# relaysch.net
KiCad netlist of a schematic drawn in EAGLE
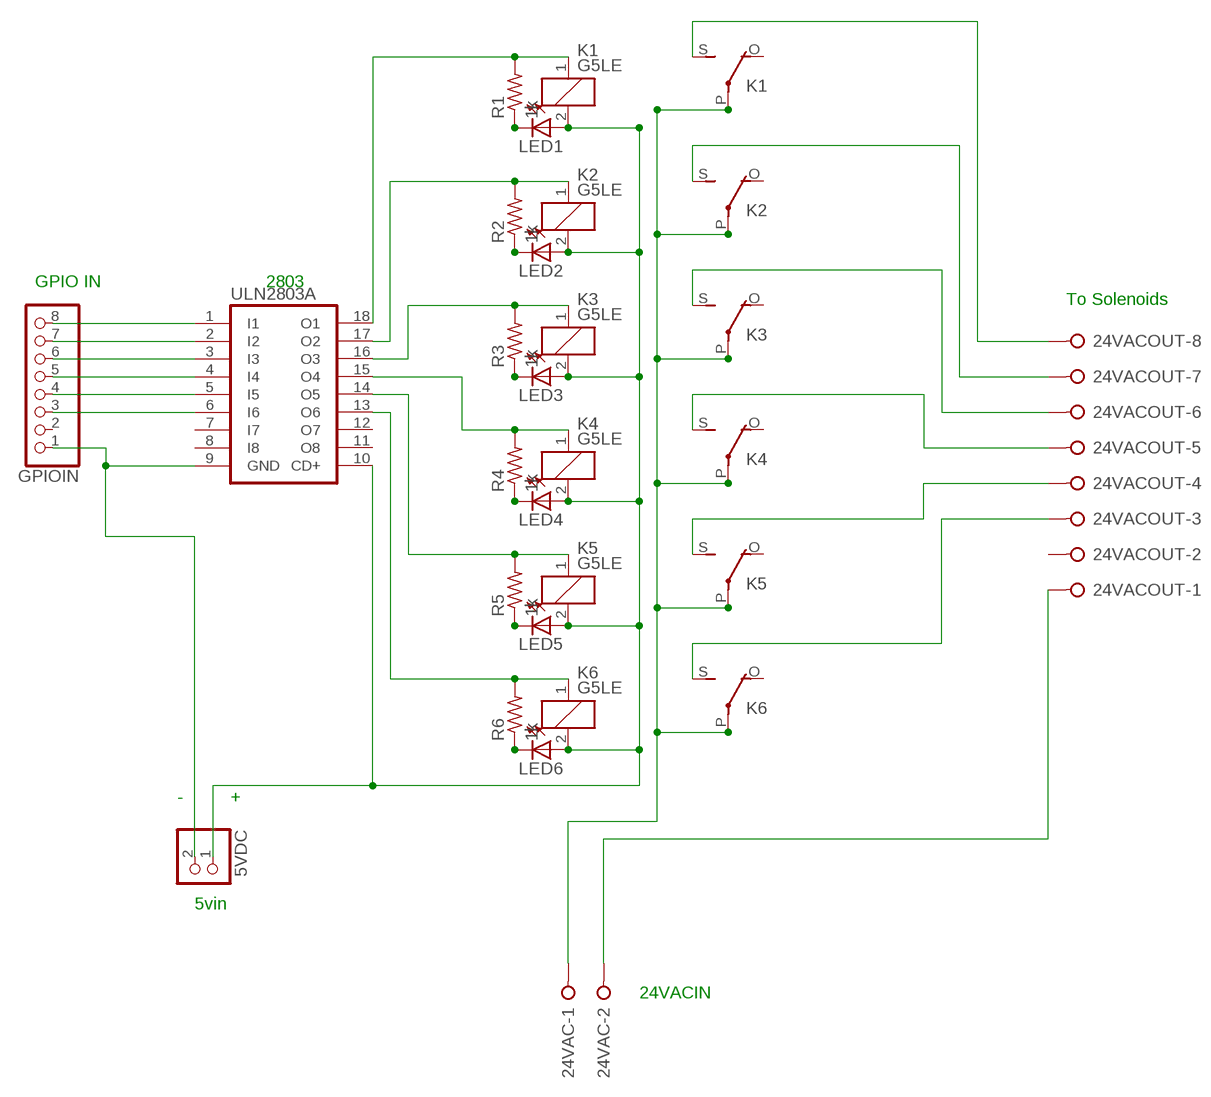
[diagram p0: schematic, sheet 1]

(export (version "E")
  (design (tool "Eeschema 10.0.6"))
  (components
    (comp (ref "5VDC")
      (value "PINHD-1X2")
      (footprint "eagle-import:1X02")
      (libsource (lib "eagle-import") (part "PINHD-1X2"))
    )
    (comp (ref "24VAC")
      (value "W237-02P")
      (footprint "eagle-import:W237-132")
      (libsource (lib "eagle-import") (part "W237-02P"))
    )
    (comp (ref "24VACOUT")
      (value "W237-08P")
      (footprint "eagle-import:W237-8P")
      (libsource (lib "eagle-import") (part "W237-08P"))
    )
    (comp (ref "GPIOIN")
      (value "PINHD-1X8BIG")
      (footprint "eagle-import:1X08-BIG")
      (libsource (lib "eagle-import") (part "PINHD-1X8BIG"))
    )
    (comp (ref "K1")
      (value "G5LE")
      (footprint "eagle-import:G5LE")
      (libsource (lib "eagle-import") (part "G5LE"))
    )
    (comp (ref "K2")
      (value "G5LE")
      (footprint "eagle-import:G5LE")
      (libsource (lib "eagle-import") (part "G5LE"))
    )
    (comp (ref "K3")
      (value "G5LE")
      (footprint "eagle-import:G5LE")
      (libsource (lib "eagle-import") (part "G5LE"))
    )
    (comp (ref "K4")
      (value "G5LE")
      (footprint "eagle-import:G5LE")
      (libsource (lib "eagle-import") (part "G5LE"))
    )
    (comp (ref "K5")
      (value "G5LE")
      (footprint "eagle-import:G5LE")
      (libsource (lib "eagle-import") (part "G5LE"))
    )
    (comp (ref "K6")
      (value "G5LE")
      (footprint "eagle-import:G5LE")
      (libsource (lib "eagle-import") (part "G5LE"))
    )
    (comp (ref "LED1")
      (value "LED5MM")
      (footprint "eagle-import:LED5MM")
      (libsource (lib "eagle-import") (part "LED5MM"))
    )
    (comp (ref "LED2")
      (value "LED5MM")
      (footprint "eagle-import:LED5MM")
      (libsource (lib "eagle-import") (part "LED5MM"))
    )
    (comp (ref "LED3")
      (value "LED5MM")
      (footprint "eagle-import:LED5MM")
      (libsource (lib "eagle-import") (part "LED5MM"))
    )
    (comp (ref "LED4")
      (value "LED5MM")
      (footprint "eagle-import:LED5MM")
      (libsource (lib "eagle-import") (part "LED5MM"))
    )
    (comp (ref "LED5")
      (value "LED5MM")
      (footprint "eagle-import:LED5MM")
      (libsource (lib "eagle-import") (part "LED5MM"))
    )
    (comp (ref "LED6")
      (value "LED5MM")
      (footprint "eagle-import:LED5MM")
      (libsource (lib "eagle-import") (part "LED5MM"))
    )
    (comp (ref "R1")
      (value "1k")
      (footprint "eagle-import:0805-THM")
      (libsource (lib "eagle-import") (part "FLIPFLOP-RES"))
    )
    (comp (ref "R2")
      (value "1k")
      (footprint "eagle-import:0805-THM")
      (libsource (lib "eagle-import") (part "FLIPFLOP-RES"))
    )
    (comp (ref "R3")
      (value "1k")
      (footprint "eagle-import:0805-THM")
      (libsource (lib "eagle-import") (part "FLIPFLOP-RES"))
    )
    (comp (ref "R4")
      (value "1k")
      (footprint "eagle-import:0805-THM")
      (libsource (lib "eagle-import") (part "FLIPFLOP-RES"))
    )
    (comp (ref "R5")
      (value "1k")
      (footprint "eagle-import:0805-THM")
      (libsource (lib "eagle-import") (part "FLIPFLOP-RES"))
    )
    (comp (ref "R6")
      (value "1k")
      (footprint "eagle-import:0805-THM")
      (libsource (lib "eagle-import") (part "FLIPFLOP-RES"))
    )
    (comp (ref "ULN2803A")
      (value "ULN2803A")
      (footprint "eagle-import:DIL18")
      (libsource (lib "eagle-import") (part "ULN2803A"))
    )
  )
  (nets
    (net (code "1") (name "Net-(24VACA-KL)") (class "Default")
      (node (ref "24VAC") (pin "1") (pinfunction "KL_1") (pintype "passive"))
      (node (ref "K1") (pin "P") (pinfunction "P_P") (pintype "passive"))
      (node (ref "K2") (pin "P") (pinfunction "P_P") (pintype "passive"))
      (node (ref "K3") (pin "P") (pinfunction "P_P") (pintype "passive"))
      (node (ref "K4") (pin "P") (pinfunction "P_P") (pintype "passive"))
      (node (ref "K5") (pin "P") (pinfunction "P_P") (pintype "passive"))
      (node (ref "K6") (pin "P") (pinfunction "P_P") (pintype "passive"))
    )
    (net (code "2") (name "Net-(24VACB-KL)") (class "Default")
      (node (ref "24VAC") (pin "2") (pinfunction "KL_2") (pintype "passive"))
      (node (ref "24VACOUT") (pin "1") (pinfunction "KL_1") (pintype "passive"))
    )
    (net (code "3") (name "Net-(24VACOUTC-KL)") (class "Default")
      (node (ref "24VACOUT") (pin "3") (pinfunction "KL_3") (pintype "passive"))
      (node (ref "K6") (pin "S") (pinfunction "S_S") (pintype "passive"))
    )
    (net (code "4") (name "Net-(24VACOUTD-KL)") (class "Default")
      (node (ref "24VACOUT") (pin "4") (pinfunction "KL_4") (pintype "passive"))
      (node (ref "K5") (pin "S") (pinfunction "S_S") (pintype "passive"))
    )
    (net (code "5") (name "Net-(24VACOUTE-KL)") (class "Default")
      (node (ref "24VACOUT") (pin "5") (pinfunction "KL_5") (pintype "passive"))
      (node (ref "K4") (pin "S") (pinfunction "S_S") (pintype "passive"))
    )
    (net (code "6") (name "Net-(24VACOUTF-KL)") (class "Default")
      (node (ref "24VACOUT") (pin "6") (pinfunction "KL_6") (pintype "passive"))
      (node (ref "K3") (pin "S") (pinfunction "S_S") (pintype "passive"))
    )
    (net (code "7") (name "Net-(24VACOUTG-KL)") (class "Default")
      (node (ref "24VACOUT") (pin "7") (pinfunction "KL_7") (pintype "passive"))
      (node (ref "K2") (pin "S") (pinfunction "S_S") (pintype "passive"))
    )
    (net (code "8") (name "Net-(24VACOUTH-KL)") (class "Default")
      (node (ref "24VACOUT") (pin "8") (pinfunction "KL_8") (pintype "passive"))
      (node (ref "K1") (pin "S") (pinfunction "S_S") (pintype "passive"))
    )
    (net (code "9") (name "Net-(LED1-C)") (class "Default")
      (node (ref "LED1") (pin "K") (pinfunction "C_K") (pintype "passive"))
      (node (ref "R1") (pin "1") (pinfunction "1_1") (pintype "passive"))
    )
    (net (code "10") (name "Net-(LED2-C)") (class "Default")
      (node (ref "LED2") (pin "K") (pinfunction "C_K") (pintype "passive"))
      (node (ref "R2") (pin "1") (pinfunction "1_1") (pintype "passive"))
    )
    (net (code "11") (name "Net-(LED3-C)") (class "Default")
      (node (ref "LED3") (pin "K") (pinfunction "C_K") (pintype "passive"))
      (node (ref "R3") (pin "1") (pinfunction "1_1") (pintype "passive"))
    )
    (net (code "12") (name "Net-(LED4-C)") (class "Default")
      (node (ref "LED4") (pin "K") (pinfunction "C_K") (pintype "passive"))
      (node (ref "R4") (pin "1") (pinfunction "1_1") (pintype "passive"))
    )
    (net (code "13") (name "Net-(LED5-C)") (class "Default")
      (node (ref "LED5") (pin "K") (pinfunction "C_K") (pintype "passive"))
      (node (ref "R5") (pin "1") (pinfunction "1_1") (pintype "passive"))
    )
    (net (code "14") (name "Net-(LED6-C)") (class "Default")
      (node (ref "LED6") (pin "K") (pinfunction "C_K") (pintype "passive"))
      (node (ref "R6") (pin "1") (pinfunction "1_1") (pintype "passive"))
    )
    (net (code "15") (name "Net-(ULN2803A-CD+)") (class "Default")
      (node (ref "5VDC") (pin "1") (pinfunction "1_1") (pintype "passive"))
      (node (ref "K1") (pin "2") (pinfunction "2_2") (pintype "passive"))
      (node (ref "K2") (pin "2") (pinfunction "2_2") (pintype "passive"))
      (node (ref "K3") (pin "2") (pinfunction "2_2") (pintype "passive"))
      (node (ref "K4") (pin "2") (pinfunction "2_2") (pintype "passive"))
      (node (ref "K5") (pin "2") (pinfunction "2_2") (pintype "passive"))
      (node (ref "K6") (pin "2") (pinfunction "2_2") (pintype "passive"))
      (node (ref "LED1") (pin "A") (pinfunction "A_A") (pintype "passive"))
      (node (ref "LED2") (pin "A") (pinfunction "A_A") (pintype "passive"))
      (node (ref "LED3") (pin "A") (pinfunction "A_A") (pintype "passive"))
      (node (ref "LED4") (pin "A") (pinfunction "A_A") (pintype "passive"))
      (node (ref "LED5") (pin "A") (pinfunction "A_A") (pintype "passive"))
      (node (ref "LED6") (pin "A") (pinfunction "A_A") (pintype "passive"))
      (node (ref "ULN2803A") (pin "10") (pinfunction "CD+_10") (pintype "passive"))
    )
    (net (code "16") (name "Net-(ULN2803A-GND)") (class "Default")
      (node (ref "5VDC") (pin "2") (pinfunction "2_2") (pintype "passive"))
      (node (ref "GPIOIN") (pin "1") (pinfunction "1_1") (pintype "passive"))
      (node (ref "ULN2803A") (pin "9") (pinfunction "GND_9") (pintype "power_in"))
    )
    (net (code "17") (name "Net-(ULN2803A-I1)") (class "Default")
      (node (ref "GPIOIN") (pin "8") (pinfunction "8_8") (pintype "passive"))
      (node (ref "ULN2803A") (pin "1") (pinfunction "I1_1") (pintype "input"))
    )
    (net (code "18") (name "Net-(ULN2803A-I2)") (class "Default")
      (node (ref "GPIOIN") (pin "7") (pinfunction "7_7") (pintype "passive"))
      (node (ref "ULN2803A") (pin "2") (pinfunction "I2_2") (pintype "input"))
    )
    (net (code "19") (name "Net-(ULN2803A-I3)") (class "Default")
      (node (ref "GPIOIN") (pin "6") (pinfunction "6_6") (pintype "passive"))
      (node (ref "ULN2803A") (pin "3") (pinfunction "I3_3") (pintype "input"))
    )
    (net (code "20") (name "Net-(ULN2803A-I4)") (class "Default")
      (node (ref "GPIOIN") (pin "5") (pinfunction "5_5") (pintype "passive"))
      (node (ref "ULN2803A") (pin "4") (pinfunction "I4_4") (pintype "input"))
    )
    (net (code "21") (name "Net-(ULN2803A-I5)") (class "Default")
      (node (ref "GPIOIN") (pin "4") (pinfunction "4_4") (pintype "passive"))
      (node (ref "ULN2803A") (pin "5") (pinfunction "I5_5") (pintype "input"))
    )
    (net (code "22") (name "Net-(ULN2803A-I6)") (class "Default")
      (node (ref "GPIOIN") (pin "3") (pinfunction "3_3") (pintype "passive"))
      (node (ref "ULN2803A") (pin "6") (pinfunction "I6_6") (pintype "input"))
    )
    (net (code "23") (name "Net-(ULN2803A-O1)") (class "Default")
      (node (ref "K1") (pin "1") (pinfunction "1_1") (pintype "passive"))
      (node (ref "R1") (pin "2") (pinfunction "2_2") (pintype "passive"))
      (node (ref "ULN2803A") (pin "18") (pinfunction "O1_18") (pintype "open_collector"))
    )
    (net (code "24") (name "Net-(ULN2803A-O2)") (class "Default")
      (node (ref "K2") (pin "1") (pinfunction "1_1") (pintype "passive"))
      (node (ref "R2") (pin "2") (pinfunction "2_2") (pintype "passive"))
      (node (ref "ULN2803A") (pin "17") (pinfunction "O2_17") (pintype "open_collector"))
    )
    (net (code "25") (name "Net-(ULN2803A-O3)") (class "Default")
      (node (ref "K3") (pin "1") (pinfunction "1_1") (pintype "passive"))
      (node (ref "R3") (pin "2") (pinfunction "2_2") (pintype "passive"))
      (node (ref "ULN2803A") (pin "16") (pinfunction "O3_16") (pintype "open_collector"))
    )
    (net (code "26") (name "Net-(ULN2803A-O4)") (class "Default")
      (node (ref "K4") (pin "1") (pinfunction "1_1") (pintype "passive"))
      (node (ref "R4") (pin "2") (pinfunction "2_2") (pintype "passive"))
      (node (ref "ULN2803A") (pin "15") (pinfunction "O4_15") (pintype "open_collector"))
    )
    (net (code "27") (name "Net-(ULN2803A-O5)") (class "Default")
      (node (ref "K5") (pin "1") (pinfunction "1_1") (pintype "passive"))
      (node (ref "R5") (pin "2") (pinfunction "2_2") (pintype "passive"))
      (node (ref "ULN2803A") (pin "14") (pinfunction "O5_14") (pintype "open_collector"))
    )
    (net (code "28") (name "Net-(ULN2803A-O6)") (class "Default")
      (node (ref "K6") (pin "1") (pinfunction "1_1") (pintype "passive"))
      (node (ref "R6") (pin "2") (pinfunction "2_2") (pintype "passive"))
      (node (ref "ULN2803A") (pin "13") (pinfunction "O6_13") (pintype "open_collector"))
    )
    (net (code "29") (name "unconnected-(24VACOUTB-KL-Pad2)") (class "Default")
      (node (ref "24VACOUT") (pin "2") (pinfunction "KL_2") (pintype "passive"))
    )
    (net (code "30") (name "unconnected-(GPIOIN-Pad2)") (class "Default")
      (node (ref "GPIOIN") (pin "2") (pinfunction "2_2") (pintype "passive"))
    )
    (net (code "31") (name "unconnected-(K1-PadO)") (class "Default")
      (node (ref "K1") (pin "O") (pinfunction "O_O") (pintype "passive"))
    )
    (net (code "32") (name "unconnected-(K2-PadO)") (class "Default")
      (node (ref "K2") (pin "O") (pinfunction "O_O") (pintype "passive"))
    )
    (net (code "33") (name "unconnected-(K3-PadO)") (class "Default")
      (node (ref "K3") (pin "O") (pinfunction "O_O") (pintype "passive"))
    )
    (net (code "34") (name "unconnected-(K4-PadO)") (class "Default")
      (node (ref "K4") (pin "O") (pinfunction "O_O") (pintype "passive"))
    )
    (net (code "35") (name "unconnected-(K5-PadO)") (class "Default")
      (node (ref "K5") (pin "O") (pinfunction "O_O") (pintype "passive"))
    )
    (net (code "36") (name "unconnected-(K6-PadO)") (class "Default")
      (node (ref "K6") (pin "O") (pinfunction "O_O") (pintype "passive"))
    )
    (net (code "37") (name "unconnected-(ULN2803A-I7-Pad7)") (class "Default")
      (node (ref "ULN2803A") (pin "7") (pinfunction "I7_7") (pintype "input"))
    )
    (net (code "38") (name "unconnected-(ULN2803A-I8-Pad8)") (class "Default")
      (node (ref "ULN2803A") (pin "8") (pinfunction "I8_8") (pintype "input"))
    )
    (net (code "39") (name "unconnected-(ULN2803A-O7-Pad12)") (class "Default")
      (node (ref "ULN2803A") (pin "12") (pinfunction "O7_12") (pintype "open_collector"))
    )
    (net (code "40") (name "unconnected-(ULN2803A-O8-Pad11)") (class "Default")
      (node (ref "ULN2803A") (pin "11") (pinfunction "O8_11") (pintype "open_collector"))
    )
  )
)
